# energy_router_panel__3.net
KiCad netlist of a schematic drawn in Altium Designer
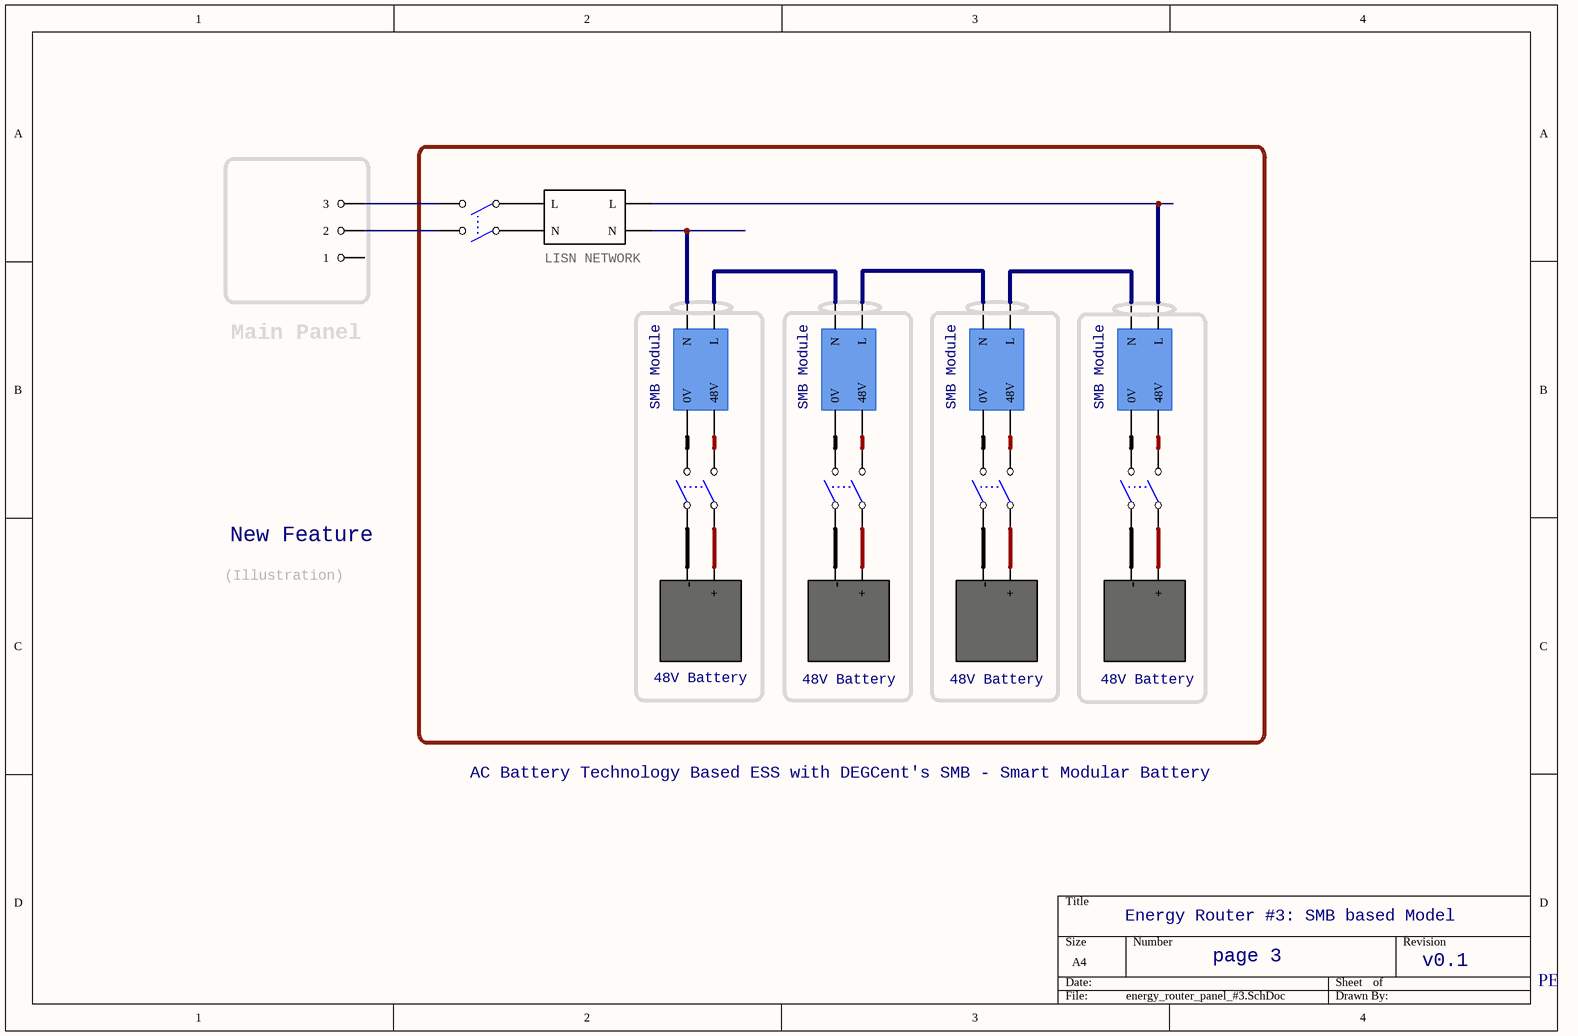
[diagram p0: energy_router_panel_#3.SchDoc]

(export (version "E")
  (design (tool "Eeschema 10.0.6"))
  (components
    (comp (ref "300")
      (value "3 HEADER")
      (description "3 Pin Header")
      (libsource (lib "myzou") (part "3 HEADER"))
    )
    (comp (ref "Battery 301") (value "48V Battery") (libsource (lib "Schlib-ORES") (part "1_BAT_48V")))
    (comp (ref "Battery 303") (value "48V Battery") (libsource (lib "Schlib-ORES") (part "1_BAT_48V")))
    (comp (ref "Battery 304") (value "48V Battery") (libsource (lib "Schlib-ORES") (part "1_BAT_48V")))
    (comp (ref "Battery302") (value "48V Battery") (libsource (lib "Schlib-ORES") (part "1_BAT_48V")))
    (comp (ref "K300") (value "Switch") (libsource (lib "开关") (part "SW-DPST")))
    (comp (ref "K301") (value "Switch") (libsource (lib "开关") (part "SW-DPST")))
    (comp (ref "K302") (value "Switch") (libsource (lib "开关") (part "SW-DPST")))
    (comp (ref "K303") (value "Switch") (libsource (lib "开关") (part "SW-DPST")))
    (comp (ref "K304") (value "Switch") (libsource (lib "开关") (part "SW-DPST")))
    (comp (ref "U301") (value "SMB Module") (libsource (lib "Schlib-ORES") (part "20_SMB_Module")))
    (comp (ref "U302") (value "SMB Module") (libsource (lib "Schlib-ORES") (part "20_SMB_Module")))
    (comp (ref "U303") (value "SMB Module") (libsource (lib "Schlib-ORES") (part "20_SMB_Module")))
    (comp (ref "U304") (value "SMB Module") (libsource (lib "Schlib-ORES") (part "20_SMB_Module")))
    (comp (ref "U321") (value "LISN NETWORK") (libsource (lib "Schlib-ORES") (part "21_LISN_NETWORK")))
  )
  (nets
    (net (code "1") (name "Net-(300-Pad2)") (class "Default")
      (node (ref "300") (pin "2") (pinfunction "2_2") (pintype "passive"))
      (node (ref "K300") (pin "2") (pinfunction "2_2") (pintype "passive"))
    )
    (net (code "2") (name "Net-(300-Pad3)") (class "Default")
      (node (ref "300") (pin "3") (pinfunction "3_3") (pintype "passive"))
      (node (ref "K300") (pin "4") (pinfunction "4_4") (pintype "passive"))
    )
    (net (code "3") (name "Net-(Battery 301-+)") (class "Default")
      (node (ref "Battery 301") (pin "2") (pinfunction "+_2") (pintype "passive"))
      (node (ref "K301") (pin "3") (pinfunction "3_3") (pintype "passive"))
    )
    (net (code "4") (name "Net-(Battery 301--)") (class "Default")
      (node (ref "Battery 301") (pin "1") (pinfunction "-_1") (pintype "passive"))
      (node (ref "K301") (pin "1") (pinfunction "1_1") (pintype "passive"))
    )
    (net (code "5") (name "Net-(Battery 303-+)") (class "Default")
      (node (ref "Battery 303") (pin "2") (pinfunction "+_2") (pintype "passive"))
      (node (ref "K303") (pin "3") (pinfunction "3_3") (pintype "passive"))
    )
    (net (code "6") (name "Net-(Battery 303--)") (class "Default")
      (node (ref "Battery 303") (pin "1") (pinfunction "-_1") (pintype "passive"))
      (node (ref "K303") (pin "1") (pinfunction "1_1") (pintype "passive"))
    )
    (net (code "7") (name "Net-(Battery 304-+)") (class "Default")
      (node (ref "Battery 304") (pin "2") (pinfunction "+_2") (pintype "passive"))
      (node (ref "K304") (pin "3") (pinfunction "3_3") (pintype "passive"))
    )
    (net (code "8") (name "Net-(Battery 304--)") (class "Default")
      (node (ref "Battery 304") (pin "1") (pinfunction "-_1") (pintype "passive"))
      (node (ref "K304") (pin "1") (pinfunction "1_1") (pintype "passive"))
    )
    (net (code "9") (name "Net-(Battery302-+)") (class "Default")
      (node (ref "Battery302") (pin "2") (pinfunction "+_2") (pintype "passive"))
      (node (ref "K302") (pin "3") (pinfunction "3_3") (pintype "passive"))
    )
    (net (code "10") (name "Net-(Battery302--)") (class "Default")
      (node (ref "Battery302") (pin "1") (pinfunction "-_1") (pintype "passive"))
      (node (ref "K302") (pin "1") (pinfunction "1_1") (pintype "passive"))
    )
    (net (code "11") (name "Net-(U301-0V)") (class "Default")
      (node (ref "K301") (pin "2") (pinfunction "2_2") (pintype "passive"))
      (node (ref "U301") (pin "4") (pinfunction "0V_4") (pintype "passive"))
    )
    (net (code "12") (name "Net-(U301-48V)") (class "Default")
      (node (ref "K301") (pin "4") (pinfunction "4_4") (pintype "passive"))
      (node (ref "U301") (pin "5") (pinfunction "48V_5") (pintype "passive"))
    )
    (net (code "13") (name "Net-(U301-L)") (class "Default")
      (node (ref "U301") (pin "2") (pinfunction "L_2") (pintype "passive"))
      (node (ref "U302") (pin "1") (pinfunction "N_1") (pintype "passive"))
    )
    (net (code "14") (name "Net-(U301-N)") (class "Default")
      (node (ref "U301") (pin "1") (pinfunction "N_1") (pintype "passive"))
      (node (ref "U321") (pin "4") (pinfunction "N_4") (pintype "passive"))
    )
    (net (code "15") (name "Net-(U302-0V)") (class "Default")
      (node (ref "K302") (pin "2") (pinfunction "2_2") (pintype "passive"))
      (node (ref "U302") (pin "4") (pinfunction "0V_4") (pintype "passive"))
    )
    (net (code "16") (name "Net-(U302-48V)") (class "Default")
      (node (ref "K302") (pin "4") (pinfunction "4_4") (pintype "passive"))
      (node (ref "U302") (pin "5") (pinfunction "48V_5") (pintype "passive"))
    )
    (net (code "17") (name "Net-(U302-L)") (class "Default")
      (node (ref "U302") (pin "2") (pinfunction "L_2") (pintype "passive"))
      (node (ref "U303") (pin "1") (pinfunction "N_1") (pintype "passive"))
    )
    (net (code "18") (name "Net-(U303-0V)") (class "Default")
      (node (ref "K303") (pin "2") (pinfunction "2_2") (pintype "passive"))
      (node (ref "U303") (pin "4") (pinfunction "0V_4") (pintype "passive"))
    )
    (net (code "19") (name "Net-(U303-48V)") (class "Default")
      (node (ref "K303") (pin "4") (pinfunction "4_4") (pintype "passive"))
      (node (ref "U303") (pin "5") (pinfunction "48V_5") (pintype "passive"))
    )
    (net (code "20") (name "Net-(U303-L)") (class "Default")
      (node (ref "U303") (pin "2") (pinfunction "L_2") (pintype "passive"))
      (node (ref "U304") (pin "1") (pinfunction "N_1") (pintype "passive"))
    )
    (net (code "21") (name "Net-(U304-0V)") (class "Default")
      (node (ref "K304") (pin "2") (pinfunction "2_2") (pintype "passive"))
      (node (ref "U304") (pin "4") (pinfunction "0V_4") (pintype "passive"))
    )
    (net (code "22") (name "Net-(U304-48V)") (class "Default")
      (node (ref "K304") (pin "4") (pinfunction "4_4") (pintype "passive"))
      (node (ref "U304") (pin "5") (pinfunction "48V_5") (pintype "passive"))
    )
    (net (code "23") (name "Net-(U304-L)") (class "Default")
      (node (ref "U304") (pin "2") (pinfunction "L_2") (pintype "passive"))
      (node (ref "U321") (pin "5") (pinfunction "L_5") (pintype "passive"))
    )
    (net (code "24") (name "unconnected-(300-Pad1)") (class "Default")
      (node (ref "300") (pin "1") (pinfunction "1_1") (pintype "passive"))
    )
    (net (code "25") (name "unconnected-(K300-Pad1)") (class "Default")
      (node (ref "K300") (pin "1") (pinfunction "1_1") (pintype "passive"))
    )
    (net (code "26") (name "unconnected-(K300-Pad3)") (class "Default")
      (node (ref "K300") (pin "3") (pinfunction "3_3") (pintype "passive"))
    )
    (net (code "27") (name "unconnected-(U321-L-Pad2)") (class "Default")
      (node (ref "U321") (pin "2") (pinfunction "L_2") (pintype "passive"))
    )
    (net (code "28") (name "unconnected-(U321-N-Pad1)") (class "Default")
      (node (ref "U321") (pin "1") (pinfunction "N_1") (pintype "passive"))
    )
  )
)
